# TLC5620.net
KiCad netlist of a schematic drawn in EasyEDA Pro
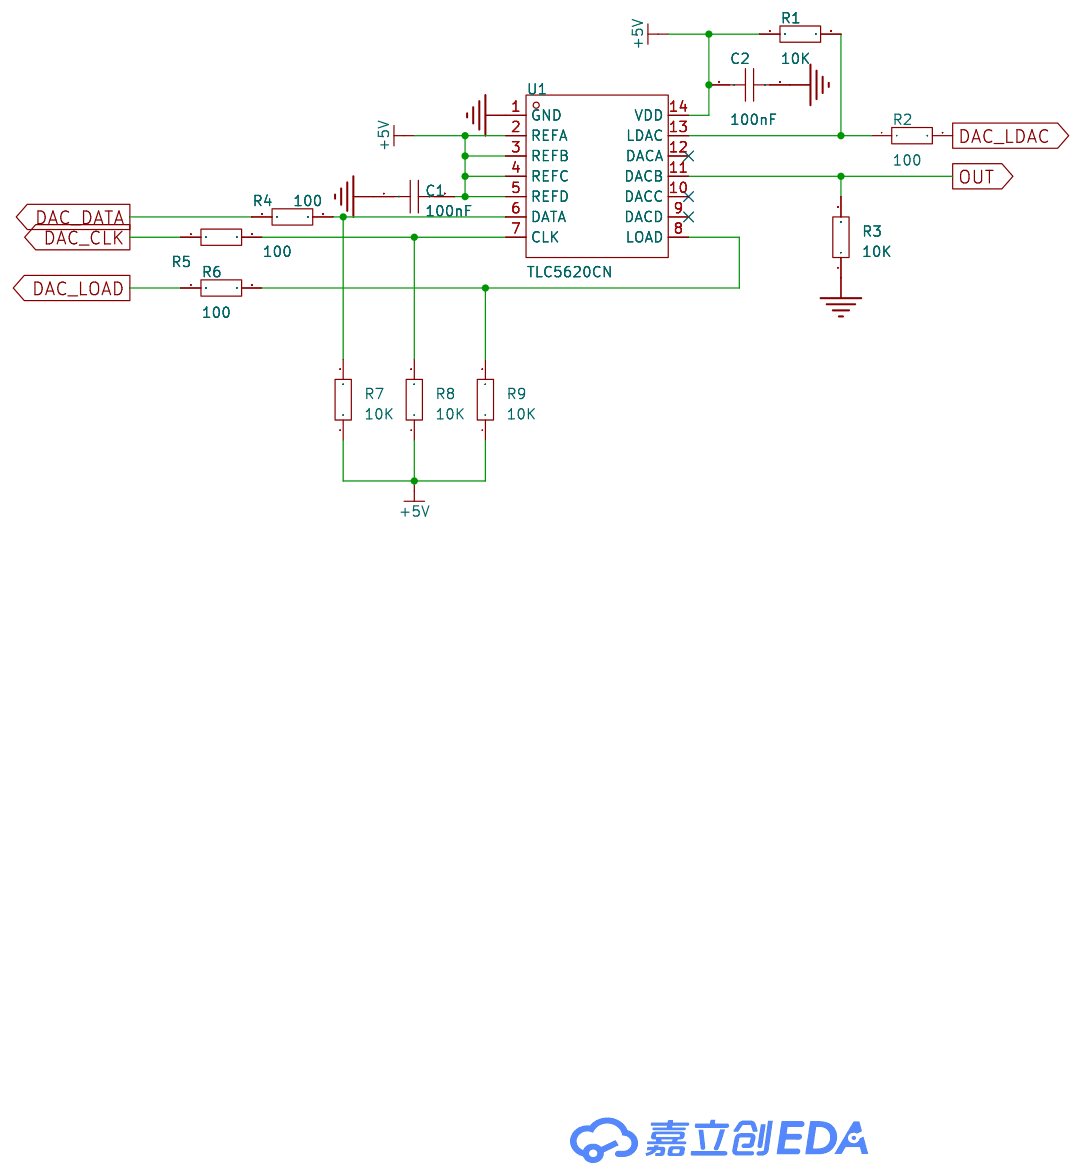
[diagram p0: schematic sheet]

(export (version "E")
  (design (tool "Eeschema 10.0.6"))
  (components
    (comp (ref "C1")
      (value "100nF")
      (footprint "easyedapro:C0603")
      (libsource (lib "easyedapro") (part "CapAcitance"))
    )
    (comp (ref "C2")
      (value "100nF")
      (footprint "easyedapro:C0603")
      (libsource (lib "easyedapro") (part "CapAcitance"))
    )
    (comp (ref "R1") (value "10K") (footprint "easyedapro:R0603") (libsource (lib "easyedapro") (part "电阻")))
    (comp (ref "R2") (value "100") (footprint "easyedapro:R0603") (libsource (lib "easyedapro") (part "电阻")))
    (comp (ref "R3") (value "10K") (footprint "easyedapro:R0603") (libsource (lib "easyedapro") (part "电阻")))
    (comp (ref "R4") (value "100") (footprint "easyedapro:R0603") (libsource (lib "easyedapro") (part "电阻")))
    (comp (ref "R5") (value "100") (footprint "easyedapro:R0603") (libsource (lib "easyedapro") (part "电阻")))
    (comp (ref "R6") (value "100") (footprint "easyedapro:R0603") (libsource (lib "easyedapro") (part "电阻")))
    (comp (ref "R7") (value "10K") (footprint "easyedapro:R0603") (libsource (lib "easyedapro") (part "电阻")))
    (comp (ref "R8") (value "10K") (footprint "easyedapro:R0603") (libsource (lib "easyedapro") (part "电阻")))
    (comp (ref "R9") (value "10K") (footprint "easyedapro:R0603") (libsource (lib "easyedapro") (part "电阻")))
    (comp (ref "U1")
      (value "TLC5620CN")
      (footprint "easyedapro:DIP-14_L19.0-W7.0-P2.54-LS7.6-BL")
      (description "接口:SPI;电源电压:5V;分辨率:8位;INL/DNL:±0.9LSB；±1LSB;稳定时间:10us;")
      (fields (field (name "Manufacturer") "TI(德州仪器)"))
      (libsource (lib "easyedapro") (part "TLC5620CN"))
    )
  )
  (nets
    (net (code "1") (name "+5V") (class "Default")
      (node (ref "C1") (pin "2") (pinfunction "2_2") (pintype "input"))
      (node (ref "C2") (pin "1") (pinfunction "1_1") (pintype "input"))
      (node (ref "R1") (pin "1") (pinfunction "1_1") (pintype "input"))
      (node (ref "R7") (pin "1") (pinfunction "1_1") (pintype "input"))
      (node (ref "R8") (pin "1") (pinfunction "1_1") (pintype "input"))
      (node (ref "R9") (pin "1") (pinfunction "1_1") (pintype "input"))
      (node (ref "U1") (pin "14") (pinfunction "VDD_14") (pintype "unspecified"))
      (node (ref "U1") (pin "2") (pinfunction "REFA_2") (pintype "unspecified"))
      (node (ref "U1") (pin "3") (pinfunction "REFB_3") (pintype "unspecified"))
      (node (ref "U1") (pin "4") (pinfunction "REFC_4") (pintype "unspecified"))
      (node (ref "U1") (pin "5") (pinfunction "REFD_5") (pintype "unspecified"))
    )
    (net (code "2") (name "DAC_CLK") (class "Default")
      (node (ref "R5") (pin "1") (pinfunction "1_1") (pintype "input"))
    )
    (net (code "3") (name "DAC_DATA") (class "Default")
      (node (ref "R4") (pin "1") (pinfunction "1_1") (pintype "input"))
    )
    (net (code "4") (name "DAC_LDAC") (class "Default")
      (node (ref "R2") (pin "2") (pinfunction "2_2") (pintype "input"))
    )
    (net (code "5") (name "DAC_LOAD") (class "Default")
      (node (ref "R6") (pin "1") (pinfunction "1_1") (pintype "input"))
    )
    (net (code "6") (name "GND") (class "Default")
      (node (ref "C1") (pin "1") (pinfunction "1_1") (pintype "input"))
      (node (ref "C2") (pin "2") (pinfunction "2_2") (pintype "input"))
      (node (ref "R3") (pin "1") (pinfunction "1_1") (pintype "input"))
      (node (ref "U1") (pin "1") (pinfunction "GND_1") (pintype "unspecified"))
    )
    (net (code "7") (name "Net-(U1-CLK)") (class "Default")
      (node (ref "R5") (pin "2") (pinfunction "2_2") (pintype "input"))
      (node (ref "R8") (pin "2") (pinfunction "2_2") (pintype "input"))
      (node (ref "U1") (pin "7") (pinfunction "CLK_7") (pintype "unspecified"))
    )
    (net (code "8") (name "Net-(U1-DATA)") (class "Default")
      (node (ref "R4") (pin "2") (pinfunction "2_2") (pintype "input"))
      (node (ref "R7") (pin "2") (pinfunction "2_2") (pintype "input"))
      (node (ref "U1") (pin "6") (pinfunction "DATA_6") (pintype "unspecified"))
    )
    (net (code "9") (name "Net-(U1-LDAC)") (class "Default")
      (node (ref "R1") (pin "2") (pinfunction "2_2") (pintype "input"))
      (node (ref "R2") (pin "1") (pinfunction "1_1") (pintype "input"))
      (node (ref "U1") (pin "13") (pinfunction "LDAC_13") (pintype "unspecified"))
    )
    (net (code "10") (name "Net-(U1-LOAD)") (class "Default")
      (node (ref "R6") (pin "2") (pinfunction "2_2") (pintype "input"))
      (node (ref "R9") (pin "2") (pinfunction "2_2") (pintype "input"))
      (node (ref "U1") (pin "8") (pinfunction "LOAD_8") (pintype "unspecified"))
    )
    (net (code "11") (name "OUT") (class "Default")
      (node (ref "R3") (pin "2") (pinfunction "2_2") (pintype "input"))
      (node (ref "U1") (pin "11") (pinfunction "DACB_11") (pintype "unspecified"))
    )
    (net (code "12") (name "unconnected-(U1-DACA-Pad12)") (class "Default")
      (node (ref "U1") (pin "12") (pinfunction "DACA_12") (pintype "unspecified+no_connect"))
    )
    (net (code "13") (name "unconnected-(U1-DACC-Pad10)") (class "Default")
      (node (ref "U1") (pin "10") (pinfunction "DACC_10") (pintype "unspecified+no_connect"))
    )
    (net (code "14") (name "unconnected-(U1-DACD-Pad9)") (class "Default")
      (node (ref "U1") (pin "9") (pinfunction "DACD_9") (pintype "unspecified+no_connect"))
    )
  )
)
